# VoltageRegulator.net
KiCad netlist of a schematic drawn in Altium Designer
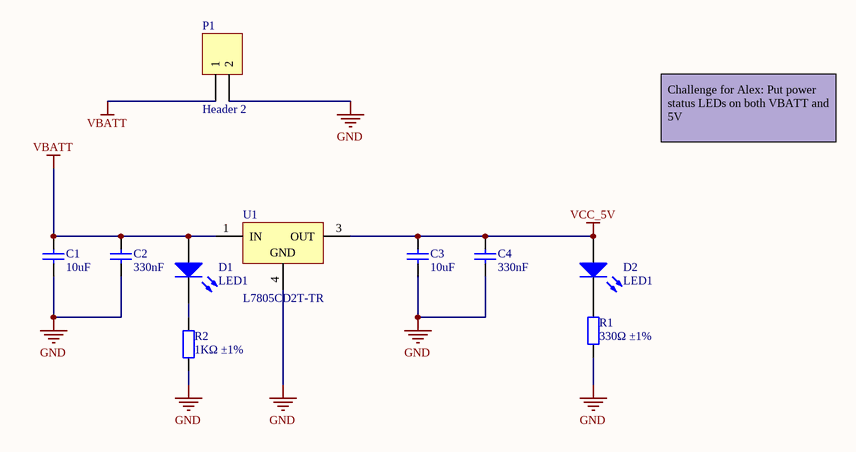
[diagram p0: VoltageRegulator.SchDoc]

(export (version "E")
  (design (tool "Eeschema 10.0.6"))
  (components
    (comp (ref "C1")
      (value "10uF")
      (footprint "1206_C")
      (description "Chip capacitors")
      (fields
        (field (name "MANUFACTURER") "Samsung Electro-Mechanics")
        (field (name "PARTNUMBER") "CL31A106KBHNNNE")
      )
      (libsource (lib "Cap") (part "1206 10uF (106) 10% 50V"))
    )
    (comp (ref "C2")
      (value "330nF")
      (footprint "0603_C")
      (description "Chip capacitors")
      (fields
        (field (name "MANUFACTURER") "Guangdong Fenghua Advanced Tech")
        (field (name "PARTNUMBER") "0603B334K250NT")
      )
      (libsource (lib "Cap") (part "0603 330nF (334) 10% 25V"))
    )
    (comp (ref "C3")
      (value "10uF")
      (footprint "1206_C")
      (description "Chip capacitors")
      (fields
        (field (name "MANUFACTURER") "Samsung Electro-Mechanics")
        (field (name "PARTNUMBER") "CL31A106KBHNNNE")
      )
      (libsource (lib "Cap") (part "1206 10uF (106) 10% 50V"))
    )
    (comp (ref "C4")
      (value "330nF")
      (footprint "0603_C")
      (description "Chip capacitors")
      (fields
        (field (name "MANUFACTURER") "Guangdong Fenghua Advanced Tech")
        (field (name "PARTNUMBER") "0603B334K250NT")
      )
      (libsource (lib "Cap") (part "0603 330nF (334) 10% 25V"))
    )
    (comp (ref "D1")
      (value "LED1")
      (footprint "LED-1")
      (description "Typical RED GaAs LED")
      (fields (field (name "PUBLISHER") "Altium Limited"))
      (libsource (lib "Miscellaneous Devices") (part "LED1"))
    )
    (comp (ref "D2")
      (value "LED1")
      (footprint "LED-1")
      (description "Typical RED GaAs LED")
      (fields (field (name "PUBLISHER") "Altium Limited"))
      (libsource (lib "Miscellaneous Devices") (part "LED1"))
    )
    (comp (ref "P1")
      (value "Header 2")
      (footprint "HDR1X2")
      (description "Header, 2-Pin")
      (fields (field (name "PUBLISHER") "Altium Limited"))
      (libsource (lib "Miscellaneous Connectors") (part "Header 2"))
    )
    (comp (ref "R1")
      (value "330Ω ±1%")
      (footprint "0603_R")
      (description "Chip resistor")
      (fields (field (name "MANUFACTURER") "Uniroyal Elec") (field (name "PARTNUMBER") "0603WAF3300T5E"))
      (libsource (lib "RES") (part "0603 330R (3300) 1%"))
    )
    (comp (ref "R2")
      (value "1KΩ ±1%")
      (footprint "0805_R")
      (description "Chip resistor")
      (fields (field (name "MANUFACTURER") "Uniroyal Elec") (field (name "POWER") "1/8W"))
      (libsource (lib "Miscellaneous Devices LC") (part "0805 1K (1001) 1%"))
    )
    (comp (ref "U1")
      (value "L7805CD2T-TR")
      (footprint "TO-263_M")
      (description "Positive Voltage Regulator, 3-Pin D2PAK, Tape and Reel")
      (libsource (lib "Altium Content Vault") (part "PM-REG-L4940-SOT3"))
    )
  )
  (nets
    (net (code "1") (name "GND") (class "Default")
      (node (ref "C1") (pin "1") (pinfunction "1_1") (pintype "passive"))
      (node (ref "C2") (pin "1") (pinfunction "1_1") (pintype "passive"))
      (node (ref "C3") (pin "1") (pinfunction "1_1") (pintype "passive"))
      (node (ref "C4") (pin "1") (pinfunction "1_1") (pintype "passive"))
      (node (ref "P1") (pin "2") (pinfunction "2_2") (pintype "passive"))
      (node (ref "R1") (pin "2") (pinfunction "2_2") (pintype "passive"))
      (node (ref "R2") (pin "1") (pinfunction "1_1") (pintype "passive"))
      (node (ref "U1") (pin "4") (pinfunction "GND_4") (pintype "power_in"))
    )
    (net (code "2") (name "Net-(D1-K)") (class "Default")
      (node (ref "D1") (pin "2") (pinfunction "K_2") (pintype "passive"))
      (node (ref "R2") (pin "2") (pinfunction "2_2") (pintype "passive"))
    )
    (net (code "3") (name "Net-(D2-K)") (class "Default")
      (node (ref "D2") (pin "2") (pinfunction "K_2") (pintype "passive"))
      (node (ref "R1") (pin "1") (pinfunction "1_1") (pintype "passive"))
    )
    (net (code "4") (name "VBATT") (class "Default")
      (node (ref "C1") (pin "2") (pinfunction "2_2") (pintype "passive"))
      (node (ref "C2") (pin "2") (pinfunction "2_2") (pintype "passive"))
      (node (ref "D1") (pin "1") (pinfunction "A_1") (pintype "passive"))
      (node (ref "P1") (pin "1") (pinfunction "1_1") (pintype "passive"))
      (node (ref "U1") (pin "1") (pinfunction "IN_1") (pintype "power_in"))
    )
    (net (code "5") (name "VCC_5V") (class "Default")
      (node (ref "C3") (pin "2") (pinfunction "2_2") (pintype "passive"))
      (node (ref "C4") (pin "2") (pinfunction "2_2") (pintype "passive"))
      (node (ref "D2") (pin "1") (pinfunction "A_1") (pintype "passive"))
      (node (ref "U1") (pin "3") (pinfunction "OUT_3") (pintype "power_in"))
    )
  )
)
